# Debug.net
KiCad netlist of a schematic drawn in Altium Designer
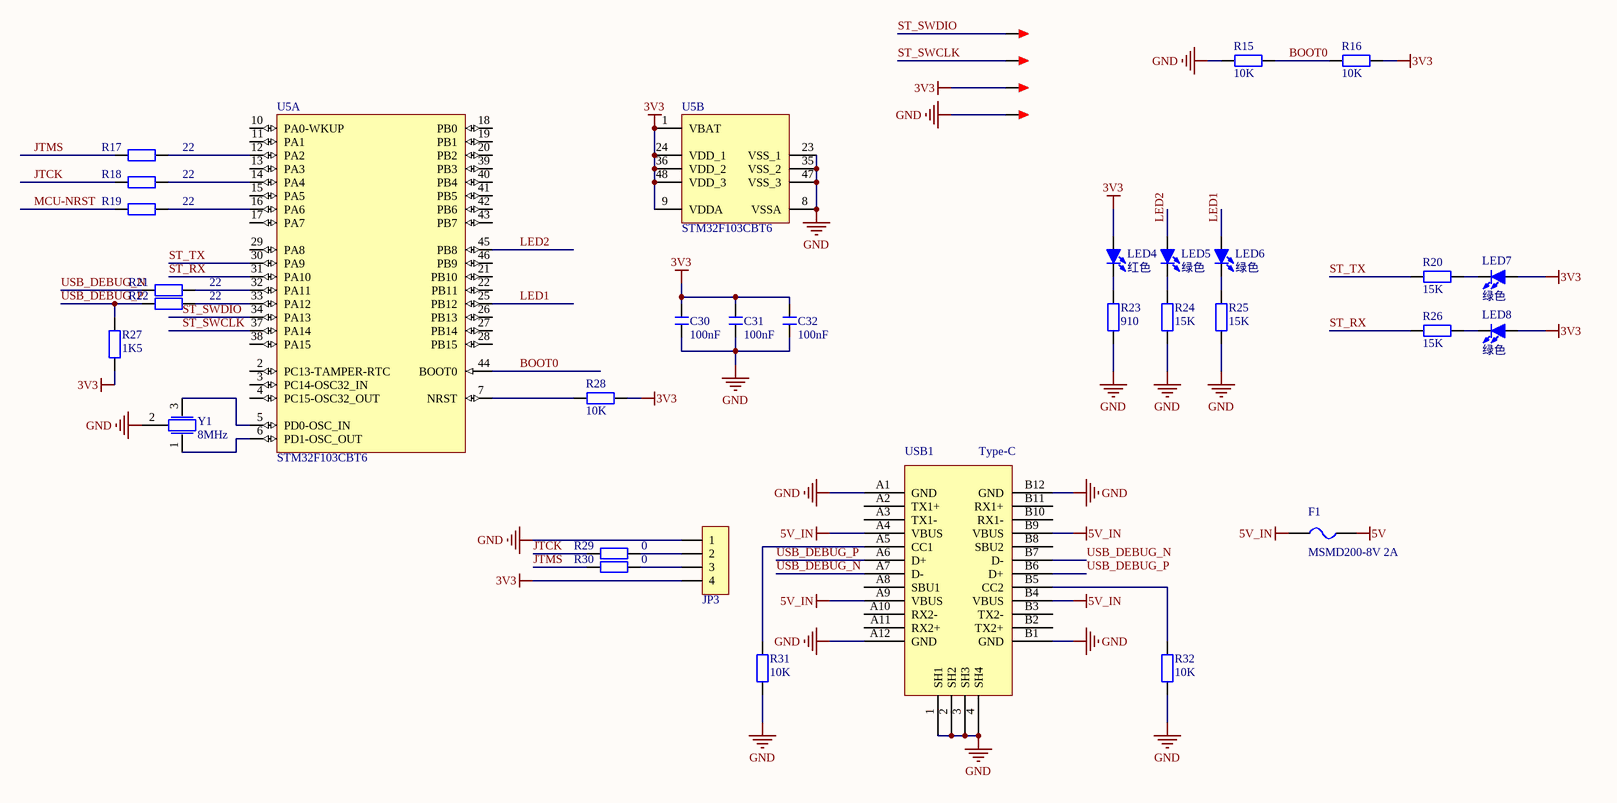
[diagram p0: Debug.SchDoc]

(export (version "E")
  (design (tool "Eeschema 10.0.6"))
  (components
    (comp (ref "C30")
      (value "100nF")
      (footprint "C 0402_L")
      (description "贴片电容")
      (libsource (lib "3.1   - 电阻-电容-电感") (part "C"))
    )
    (comp (ref "C31")
      (value "100nF")
      (footprint "C 0402_L")
      (description "贴片电容")
      (libsource (lib "3.1   - 电阻-电容-电感") (part "C"))
    )
    (comp (ref "C32")
      (value "100nF")
      (footprint "C 0402_L")
      (description "贴片电容")
      (libsource (lib "3.1   - 电阻-电容-电感") (part "C"))
    )
    (comp (ref "F1")
      (value "MSMD200-8V 2A")
      (footprint "FU 0603")
      (description "贴片保险丝")
      (libsource (lib "10.1 - 保险丝-晶振") (part "FU"))
    )
    (comp (ref "JP3")
      (value "HDR-1X4")
      (footprint "HDR2.54-WI-4P")
      (description "4P接插件")
      (libsource (lib "4.5   - 接插件-脚距2.54") (part "Header 4"))
    )
    (comp (ref "LED4")
      (value "红色")
      (footprint "LED")
      (description "C84267")
      (libsource (lib "9.1   - LED") (part "LED-SMD"))
    )
    (comp (ref "LED5")
      (value "绿色")
      (footprint "LED")
      (description "C84267")
      (libsource (lib "9.1   - LED") (part "LED-SMD"))
    )
    (comp (ref "LED6")
      (value "绿色")
      (footprint "LED")
      (description "C84267")
      (libsource (lib "9.1   - LED") (part "LED-SMD"))
    )
    (comp (ref "LED7")
      (value "绿色")
      (footprint "LED")
      (description "C84267")
      (libsource (lib "9.1   - LED") (part "LED-SMD"))
    )
    (comp (ref "LED8")
      (value "绿色")
      (footprint "LED")
      (description "C84267")
      (libsource (lib "9.1   - LED") (part "LED-SMD"))
    )
    (comp (ref "R15")
      (value "10K")
      (footprint "R 0402_L")
      (description "贴片电阻")
      (libsource (lib "3.1   - 电阻-电容-电感") (part "R"))
    )
    (comp (ref "R16")
      (value "10K")
      (footprint "R 0402_L")
      (description "贴片电阻")
      (libsource (lib "3.1   - 电阻-电容-电感") (part "R"))
    )
    (comp (ref "R17")
      (value "22")
      (footprint "R 0402_L")
      (description "贴片电阻")
      (libsource (lib "3.1   - 电阻-电容-电感") (part "R"))
    )
    (comp (ref "R18")
      (value "22")
      (footprint "R 0402_L")
      (description "贴片电阻")
      (libsource (lib "3.1   - 电阻-电容-电感") (part "R"))
    )
    (comp (ref "R19")
      (value "22")
      (footprint "R 0402_L")
      (description "贴片电阻")
      (libsource (lib "3.1   - 电阻-电容-电感") (part "R"))
    )
    (comp (ref "R20")
      (value "15K")
      (footprint "R 0402_L")
      (description "贴片电阻 0402 5%")
      (libsource (lib "3.1   - 电阻-电容-电感") (part "R"))
    )
    (comp (ref "R21")
      (value "22")
      (footprint "R 0402_L")
      (description "贴片电阻")
      (libsource (lib "3.1   - 电阻-电容-电感") (part "R"))
    )
    (comp (ref "R22")
      (value "22")
      (footprint "R 0402_L")
      (description "贴片电阻")
      (libsource (lib "3.1   - 电阻-电容-电感") (part "R"))
    )
    (comp (ref "R23")
      (value "910")
      (footprint "R 0402_L")
      (description "贴片电阻 0402 5%")
      (libsource (lib "3.1   - 电阻-电容-电感") (part "R"))
    )
    (comp (ref "R24")
      (value "15K")
      (footprint "R 0402_L")
      (description "贴片电阻 0402 5%")
      (libsource (lib "3.1   - 电阻-电容-电感") (part "R"))
    )
    (comp (ref "R25")
      (value "15K")
      (footprint "R 0402_L")
      (description "贴片电阻 0402 5%")
      (libsource (lib "3.1   - 电阻-电容-电感") (part "R"))
    )
    (comp (ref "R26")
      (value "15K")
      (footprint "R 0402_L")
      (description "贴片电阻 0402 5%")
      (libsource (lib "3.1   - 电阻-电容-电感") (part "R"))
    )
    (comp (ref "R27")
      (value "1K5")
      (footprint "R 0402_L")
      (description "贴片电阻")
      (libsource (lib "3.1   - 电阻-电容-电感") (part "R"))
    )
    (comp (ref "R28")
      (value "10K")
      (footprint "R 0402_L")
      (description "贴片电阻")
      (libsource (lib "3.1   - 电阻-电容-电感") (part "R"))
    )
    (comp (ref "R29")
      (value "0")
      (footprint "R 0402_L")
      (description "贴片电阻")
      (libsource (lib "3.1   - 电阻-电容-电感") (part "R"))
    )
    (comp (ref "R30")
      (value "0")
      (footprint "R 0402_L")
      (description "贴片电阻")
      (libsource (lib "3.1   - 电阻-电容-电感") (part "R"))
    )
    (comp (ref "R31")
      (value "10K")
      (footprint "R 0402_L")
      (description "贴片电阻")
      (libsource (lib "3.1   - 电阻-电容-电感") (part "R"))
    )
    (comp (ref "R32")
      (value "10K")
      (footprint "R 0402_L")
      (description "贴片电阻")
      (libsource (lib "3.1   - 电阻-电容-电感") (part "R"))
    )
    (comp (ref "TP1")
      (value "TEST")
      (footprint "TEST 1.2")
      (description "测试点")
      (libsource (lib "15.1 - 未分类器件") (part "TEST"))
    )
    (comp (ref "TP2")
      (value "TEST")
      (footprint "TEST 1.2")
      (description "测试点")
      (libsource (lib "15.1 - 未分类器件") (part "TEST"))
    )
    (comp (ref "TP3")
      (value "TEST")
      (footprint "TEST 1.2")
      (description "测试点")
      (libsource (lib "15.1 - 未分类器件") (part "TEST"))
    )
    (comp (ref "TP4")
      (value "TEST")
      (footprint "TEST 1.2")
      (description "测试点")
      (libsource (lib "15.1 - 未分类器件") (part "TEST"))
    )
    (comp (ref "U5")
      (value "STM32F103CBT6")
      (footprint "LQFP48-7*7")
      (libsource (lib "STMicroelectronics STM32 F1") (part "STM32F103CBT6"))
    )
    (comp (ref "USB1")
      (value "Type-C")
      (footprint "Type-c接口")
      (libsource (lib "MyPcbLib") (part "USB-Type-C-TOP"))
    )
    (comp (ref "Y1")
      (value "8MHz")
      (footprint "三脚晶振")
      (description "村田贴片")
      (libsource (lib "MyPcbLib") (part "晶振-3Pin"))
    )
  )
  (nets
    (net (code "1") (name "/BOOT0") (class "Default")
      (node (ref "R15") (pin "2") (pinfunction "2_2") (pintype "passive"))
      (node (ref "R16") (pin "2") (pinfunction "2_2") (pintype "passive"))
      (node (ref "U5") (pin "44") (pinfunction "BOOT0_44") (pintype "input"))
    )
    (net (code "2") (name "/JTCK") (class "Default")
      (node (ref "R18") (pin "2") (pinfunction "2_2") (pintype "passive"))
      (node (ref "R29") (pin "1") (pinfunction "1_1") (pintype "passive"))
    )
    (net (code "3") (name "/JTMS") (class "Default")
      (node (ref "R17") (pin "2") (pinfunction "2_2") (pintype "passive"))
      (node (ref "R30") (pin "1") (pinfunction "1_1") (pintype "passive"))
    )
    (net (code "4") (name "/LED1") (class "Default")
      (node (ref "LED6") (pin "1") (pinfunction "A_1") (pintype "passive"))
      (node (ref "U5") (pin "25") (pinfunction "PB12_25") (pintype "bidirectional"))
    )
    (net (code "5") (name "/LED2") (class "Default")
      (node (ref "LED5") (pin "1") (pinfunction "A_1") (pintype "passive"))
      (node (ref "U5") (pin "45") (pinfunction "PB8_45") (pintype "bidirectional"))
    )
    (net (code "6") (name "/MCU-NRST") (class "Default")
      (node (ref "R19") (pin "2") (pinfunction "2_2") (pintype "passive"))
    )
    (net (code "7") (name "/ST_RX") (class "Default")
      (node (ref "R26") (pin "1") (pinfunction "1_1") (pintype "passive"))
      (node (ref "U5") (pin "31") (pinfunction "PA10_31") (pintype "bidirectional"))
    )
    (net (code "8") (name "/ST_SWCLK") (class "Default")
      (node (ref "TP2") (pin "1") (pinfunction "1_1") (pintype "passive"))
      (node (ref "U5") (pin "37") (pinfunction "PA14_37") (pintype "bidirectional"))
    )
    (net (code "9") (name "/ST_SWDIO") (class "Default")
      (node (ref "TP1") (pin "1") (pinfunction "1_1") (pintype "passive"))
      (node (ref "U5") (pin "34") (pinfunction "PA13_34") (pintype "bidirectional"))
    )
    (net (code "10") (name "/ST_TX") (class "Default")
      (node (ref "R20") (pin "1") (pinfunction "1_1") (pintype "passive"))
      (node (ref "U5") (pin "30") (pinfunction "PA9_30") (pintype "bidirectional"))
    )
    (net (code "11") (name "/USB_DEBUG_N") (class "Default")
      (node (ref "R21") (pin "2") (pinfunction "2_2") (pintype "passive"))
      (node (ref "USB1") (pin "A7") (pinfunction "D-_A7") (pintype "passive"))
      (node (ref "USB1") (pin "B7") (pinfunction "D-_B7") (pintype "passive"))
    )
    (net (code "12") (name "/USB_DEBUG_P") (class "Default")
      (node (ref "R22") (pin "2") (pinfunction "2_2") (pintype "passive"))
      (node (ref "R27") (pin "1") (pinfunction "1_1") (pintype "passive"))
      (node (ref "USB1") (pin "A6") (pinfunction "D+_A6") (pintype "passive"))
      (node (ref "USB1") (pin "B6") (pinfunction "D+_B6") (pintype "passive"))
    )
    (net (code "13") (name "3V3") (class "Default")
      (node (ref "C30") (pin "2") (pinfunction "2_2") (pintype "passive"))
      (node (ref "C31") (pin "2") (pinfunction "2_2") (pintype "passive"))
      (node (ref "C32") (pin "2") (pinfunction "2_2") (pintype "passive"))
      (node (ref "JP3") (pin "4") (pinfunction "4_4") (pintype "passive"))
      (node (ref "LED4") (pin "1") (pinfunction "A_1") (pintype "passive"))
      (node (ref "LED7") (pin "1") (pinfunction "A_1") (pintype "passive"))
      (node (ref "LED8") (pin "1") (pinfunction "A_1") (pintype "passive"))
      (node (ref "R16") (pin "1") (pinfunction "1_1") (pintype "passive"))
      (node (ref "R27") (pin "2") (pinfunction "2_2") (pintype "passive"))
      (node (ref "R28") (pin "1") (pinfunction "1_1") (pintype "passive"))
      (node (ref "TP3") (pin "1") (pinfunction "1_1") (pintype "passive"))
      (node (ref "U5") (pin "1") (pinfunction "VBAT_1") (pintype "power_in"))
      (node (ref "U5") (pin "24") (pinfunction "VDD_1_24") (pintype "power_in"))
      (node (ref "U5") (pin "36") (pinfunction "VDD_2_36") (pintype "power_in"))
      (node (ref "U5") (pin "48") (pinfunction "VDD_3_48") (pintype "power_in"))
      (node (ref "U5") (pin "9") (pinfunction "VDDA_9") (pintype "power_in"))
    )
    (net (code "14") (name "5V") (class "Default")
      (node (ref "F1") (pin "2") (pinfunction "2_2") (pintype "passive"))
    )
    (net (code "15") (name "5V_IN") (class "Default")
      (node (ref "F1") (pin "1") (pinfunction "1_1") (pintype "passive"))
      (node (ref "USB1") (pin "A4") (pinfunction "VBUS_A4") (pintype "passive"))
      (node (ref "USB1") (pin "A9") (pinfunction "VBUS_A9") (pintype "passive"))
      (node (ref "USB1") (pin "B4") (pinfunction "VBUS_B4") (pintype "passive"))
      (node (ref "USB1") (pin "B9") (pinfunction "VBUS_B9") (pintype "passive"))
    )
    (net (code "16") (name "GND") (class "Default")
      (node (ref "C30") (pin "1") (pinfunction "1_1") (pintype "passive"))
      (node (ref "C31") (pin "1") (pinfunction "1_1") (pintype "passive"))
      (node (ref "C32") (pin "1") (pinfunction "1_1") (pintype "passive"))
      (node (ref "JP3") (pin "1") (pinfunction "1_1") (pintype "passive"))
      (node (ref "R15") (pin "1") (pinfunction "1_1") (pintype "passive"))
      (node (ref "R23") (pin "1") (pinfunction "1_1") (pintype "passive"))
      (node (ref "R24") (pin "1") (pinfunction "1_1") (pintype "passive"))
      (node (ref "R25") (pin "1") (pinfunction "1_1") (pintype "passive"))
      (node (ref "R31") (pin "1") (pinfunction "1_1") (pintype "passive"))
      (node (ref "R32") (pin "1") (pinfunction "1_1") (pintype "passive"))
      (node (ref "TP4") (pin "1") (pinfunction "1_1") (pintype "passive"))
      (node (ref "U5") (pin "23") (pinfunction "VSS_1_23") (pintype "power_in"))
      (node (ref "U5") (pin "35") (pinfunction "VSS_2_35") (pintype "power_in"))
      (node (ref "U5") (pin "47") (pinfunction "VSS_3_47") (pintype "power_in"))
      (node (ref "U5") (pin "8") (pinfunction "VSSA_8") (pintype "power_in"))
      (node (ref "USB1") (pin "1") (pinfunction "SH1_1") (pintype "passive"))
      (node (ref "USB1") (pin "2") (pinfunction "SH2_2") (pintype "passive"))
      (node (ref "USB1") (pin "3") (pinfunction "SH3_3") (pintype "passive"))
      (node (ref "USB1") (pin "4") (pinfunction "SH4_4") (pintype "passive"))
      (node (ref "USB1") (pin "A1") (pinfunction "GND_A1") (pintype "passive"))
      (node (ref "USB1") (pin "A12") (pinfunction "GND_A12") (pintype "passive"))
      (node (ref "USB1") (pin "B1") (pinfunction "GND_B1") (pintype "passive"))
      (node (ref "USB1") (pin "B12") (pinfunction "GND_B12") (pintype "passive"))
      (node (ref "Y1") (pin "2") (pinfunction "2_2") (pintype "passive"))
    )
    (net (code "17") (name "Net-(JP3-Pad2)") (class "Default")
      (node (ref "JP3") (pin "2") (pinfunction "2_2") (pintype "passive"))
      (node (ref "R29") (pin "2") (pinfunction "2_2") (pintype "passive"))
    )
    (net (code "18") (name "Net-(JP3-Pad3)") (class "Default")
      (node (ref "JP3") (pin "3") (pinfunction "3_3") (pintype "passive"))
      (node (ref "R30") (pin "2") (pinfunction "2_2") (pintype "passive"))
    )
    (net (code "19") (name "Net-(LED4-K)") (class "Default")
      (node (ref "LED4") (pin "2") (pinfunction "K_2") (pintype "passive"))
      (node (ref "R23") (pin "2") (pinfunction "2_2") (pintype "passive"))
    )
    (net (code "20") (name "Net-(LED5-K)") (class "Default")
      (node (ref "LED5") (pin "2") (pinfunction "K_2") (pintype "passive"))
      (node (ref "R24") (pin "2") (pinfunction "2_2") (pintype "passive"))
    )
    (net (code "21") (name "Net-(LED6-K)") (class "Default")
      (node (ref "LED6") (pin "2") (pinfunction "K_2") (pintype "passive"))
      (node (ref "R25") (pin "2") (pinfunction "2_2") (pintype "passive"))
    )
    (net (code "22") (name "Net-(LED7-K)") (class "Default")
      (node (ref "LED7") (pin "2") (pinfunction "K_2") (pintype "passive"))
      (node (ref "R20") (pin "2") (pinfunction "2_2") (pintype "passive"))
    )
    (net (code "23") (name "Net-(LED8-K)") (class "Default")
      (node (ref "LED8") (pin "2") (pinfunction "K_2") (pintype "passive"))
      (node (ref "R26") (pin "2") (pinfunction "2_2") (pintype "passive"))
    )
    (net (code "24") (name "Net-(U5A-NRST)") (class "Default")
      (node (ref "R28") (pin "2") (pinfunction "2_2") (pintype "passive"))
      (node (ref "U5") (pin "7") (pinfunction "NRST_7") (pintype "bidirectional"))
    )
    (net (code "25") (name "Net-(U5A-PA2)") (class "Default")
      (node (ref "R17") (pin "1") (pinfunction "1_1") (pintype "passive"))
      (node (ref "U5") (pin "12") (pinfunction "PA2_12") (pintype "bidirectional"))
    )
    (net (code "26") (name "Net-(U5A-PA4)") (class "Default")
      (node (ref "R18") (pin "1") (pinfunction "1_1") (pintype "passive"))
      (node (ref "U5") (pin "14") (pinfunction "PA4_14") (pintype "bidirectional"))
    )
    (net (code "27") (name "Net-(U5A-PA6)") (class "Default")
      (node (ref "R19") (pin "1") (pinfunction "1_1") (pintype "passive"))
      (node (ref "U5") (pin "16") (pinfunction "PA6_16") (pintype "bidirectional"))
    )
    (net (code "28") (name "Net-(U5A-PA11)") (class "Default")
      (node (ref "R21") (pin "1") (pinfunction "1_1") (pintype "passive"))
      (node (ref "U5") (pin "32") (pinfunction "PA11_32") (pintype "bidirectional"))
    )
    (net (code "29") (name "Net-(U5A-PA12)") (class "Default")
      (node (ref "R22") (pin "1") (pinfunction "1_1") (pintype "passive"))
      (node (ref "U5") (pin "33") (pinfunction "PA12_33") (pintype "bidirectional"))
    )
    (net (code "30") (name "Net-(U5A-PD0-OSC_IN)") (class "Default")
      (node (ref "U5") (pin "5") (pinfunction "PD0-OSC_IN_5") (pintype "bidirectional"))
      (node (ref "Y1") (pin "3") (pinfunction "3_3") (pintype "passive"))
    )
    (net (code "31") (name "Net-(U5A-PD1-OSC_OUT)") (class "Default")
      (node (ref "U5") (pin "6") (pinfunction "PD1-OSC_OUT_6") (pintype "bidirectional"))
      (node (ref "Y1") (pin "1") (pinfunction "1_1") (pintype "passive"))
    )
    (net (code "32") (name "Net-(USB1-CC1)") (class "Default")
      (node (ref "R31") (pin "2") (pinfunction "2_2") (pintype "passive"))
      (node (ref "USB1") (pin "A5") (pinfunction "CC1_A5") (pintype "passive"))
    )
    (net (code "33") (name "Net-(USB1-CC2)") (class "Default")
      (node (ref "R32") (pin "2") (pinfunction "2_2") (pintype "passive"))
      (node (ref "USB1") (pin "B5") (pinfunction "CC2_B5") (pintype "passive"))
    )
    (net (code "34") (name "unconnected-(U5A-PA0-WKUP-Pad10)") (class "Default")
      (node (ref "U5") (pin "10") (pinfunction "PA0-WKUP_10") (pintype "bidirectional"))
    )
    (net (code "35") (name "unconnected-(U5A-PA1-Pad11)") (class "Default")
      (node (ref "U5") (pin "11") (pinfunction "PA1_11") (pintype "bidirectional"))
    )
    (net (code "36") (name "unconnected-(U5A-PA3-Pad13)") (class "Default")
      (node (ref "U5") (pin "13") (pinfunction "PA3_13") (pintype "bidirectional"))
    )
    (net (code "37") (name "unconnected-(U5A-PA5-Pad15)") (class "Default")
      (node (ref "U5") (pin "15") (pinfunction "PA5_15") (pintype "bidirectional"))
    )
    (net (code "38") (name "unconnected-(U5A-PA7-Pad17)") (class "Default")
      (node (ref "U5") (pin "17") (pinfunction "PA7_17") (pintype "bidirectional"))
    )
    (net (code "39") (name "unconnected-(U5A-PA8-Pad29)") (class "Default")
      (node (ref "U5") (pin "29") (pinfunction "PA8_29") (pintype "bidirectional"))
    )
    (net (code "40") (name "unconnected-(U5A-PA15-Pad38)") (class "Default")
      (node (ref "U5") (pin "38") (pinfunction "PA15_38") (pintype "bidirectional"))
    )
    (net (code "41") (name "unconnected-(U5A-PB0-Pad18)") (class "Default")
      (node (ref "U5") (pin "18") (pinfunction "PB0_18") (pintype "bidirectional"))
    )
    (net (code "42") (name "unconnected-(U5A-PB1-Pad19)") (class "Default")
      (node (ref "U5") (pin "19") (pinfunction "PB1_19") (pintype "bidirectional"))
    )
    (net (code "43") (name "unconnected-(U5A-PB2-Pad20)") (class "Default")
      (node (ref "U5") (pin "20") (pinfunction "PB2_20") (pintype "bidirectional"))
    )
    (net (code "44") (name "unconnected-(U5A-PB3-Pad39)") (class "Default")
      (node (ref "U5") (pin "39") (pinfunction "PB3_39") (pintype "bidirectional"))
    )
    (net (code "45") (name "unconnected-(U5A-PB4-Pad40)") (class "Default")
      (node (ref "U5") (pin "40") (pinfunction "PB4_40") (pintype "bidirectional"))
    )
    (net (code "46") (name "unconnected-(U5A-PB5-Pad41)") (class "Default")
      (node (ref "U5") (pin "41") (pinfunction "PB5_41") (pintype "bidirectional"))
    )
    (net (code "47") (name "unconnected-(U5A-PB6-Pad42)") (class "Default")
      (node (ref "U5") (pin "42") (pinfunction "PB6_42") (pintype "bidirectional"))
    )
    (net (code "48") (name "unconnected-(U5A-PB7-Pad43)") (class "Default")
      (node (ref "U5") (pin "43") (pinfunction "PB7_43") (pintype "bidirectional"))
    )
    (net (code "49") (name "unconnected-(U5A-PB9-Pad46)") (class "Default")
      (node (ref "U5") (pin "46") (pinfunction "PB9_46") (pintype "bidirectional"))
    )
    (net (code "50") (name "unconnected-(U5A-PB10-Pad21)") (class "Default")
      (node (ref "U5") (pin "21") (pinfunction "PB10_21") (pintype "bidirectional"))
    )
    (net (code "51") (name "unconnected-(U5A-PB11-Pad22)") (class "Default")
      (node (ref "U5") (pin "22") (pinfunction "PB11_22") (pintype "bidirectional"))
    )
    (net (code "52") (name "unconnected-(U5A-PB13-Pad26)") (class "Default")
      (node (ref "U5") (pin "26") (pinfunction "PB13_26") (pintype "bidirectional"))
    )
    (net (code "53") (name "unconnected-(U5A-PB14-Pad27)") (class "Default")
      (node (ref "U5") (pin "27") (pinfunction "PB14_27") (pintype "bidirectional"))
    )
    (net (code "54") (name "unconnected-(U5A-PB15-Pad28)") (class "Default")
      (node (ref "U5") (pin "28") (pinfunction "PB15_28") (pintype "bidirectional"))
    )
    (net (code "55") (name "unconnected-(U5A-PC13-TAMPER-RTC-Pad2)") (class "Default")
      (node (ref "U5") (pin "2") (pinfunction "PC13-TAMPER-RTC_2") (pintype "bidirectional"))
    )
    (net (code "56") (name "unconnected-(U5A-PC14-OSC32_IN-Pad3)") (class "Default")
      (node (ref "U5") (pin "3") (pinfunction "PC14-OSC32_IN_3") (pintype "bidirectional"))
    )
    (net (code "57") (name "unconnected-(U5A-PC15-OSC32_OUT-Pad4)") (class "Default")
      (node (ref "U5") (pin "4") (pinfunction "PC15-OSC32_OUT_4") (pintype "bidirectional"))
    )
    (net (code "58") (name "unconnected-(USB1-RX1+-PadB11)") (class "Default")
      (node (ref "USB1") (pin "B11") (pinfunction "RX1+_B11") (pintype "passive"))
    )
    (net (code "59") (name "unconnected-(USB1-RX1--PadB10)") (class "Default")
      (node (ref "USB1") (pin "B10") (pinfunction "RX1-_B10") (pintype "passive"))
    )
    (net (code "60") (name "unconnected-(USB1-RX2+-PadA11)") (class "Default")
      (node (ref "USB1") (pin "A11") (pinfunction "RX2+_A11") (pintype "passive"))
    )
    (net (code "61") (name "unconnected-(USB1-RX2--PadA10)") (class "Default")
      (node (ref "USB1") (pin "A10") (pinfunction "RX2-_A10") (pintype "passive"))
    )
    (net (code "62") (name "unconnected-(USB1-SBU1-PadA8)") (class "Default")
      (node (ref "USB1") (pin "A8") (pinfunction "SBU1_A8") (pintype "passive"))
    )
    (net (code "63") (name "unconnected-(USB1-SBU2-PadB8)") (class "Default")
      (node (ref "USB1") (pin "B8") (pinfunction "SBU2_B8") (pintype "passive"))
    )
    (net (code "64") (name "unconnected-(USB1-TX1+-PadA2)") (class "Default")
      (node (ref "USB1") (pin "A2") (pinfunction "TX1+_A2") (pintype "passive"))
    )
    (net (code "65") (name "unconnected-(USB1-TX1--PadA3)") (class "Default")
      (node (ref "USB1") (pin "A3") (pinfunction "TX1-_A3") (pintype "passive"))
    )
    (net (code "66") (name "unconnected-(USB1-TX2+-PadB2)") (class "Default")
      (node (ref "USB1") (pin "B2") (pinfunction "TX2+_B2") (pintype "passive"))
    )
    (net (code "67") (name "unconnected-(USB1-TX2--PadB3)") (class "Default")
      (node (ref "USB1") (pin "B3") (pinfunction "TX2-_B3") (pintype "passive"))
    )
  )
)
